# monitoring.net
KiCad netlist of a schematic drawn in EAGLE
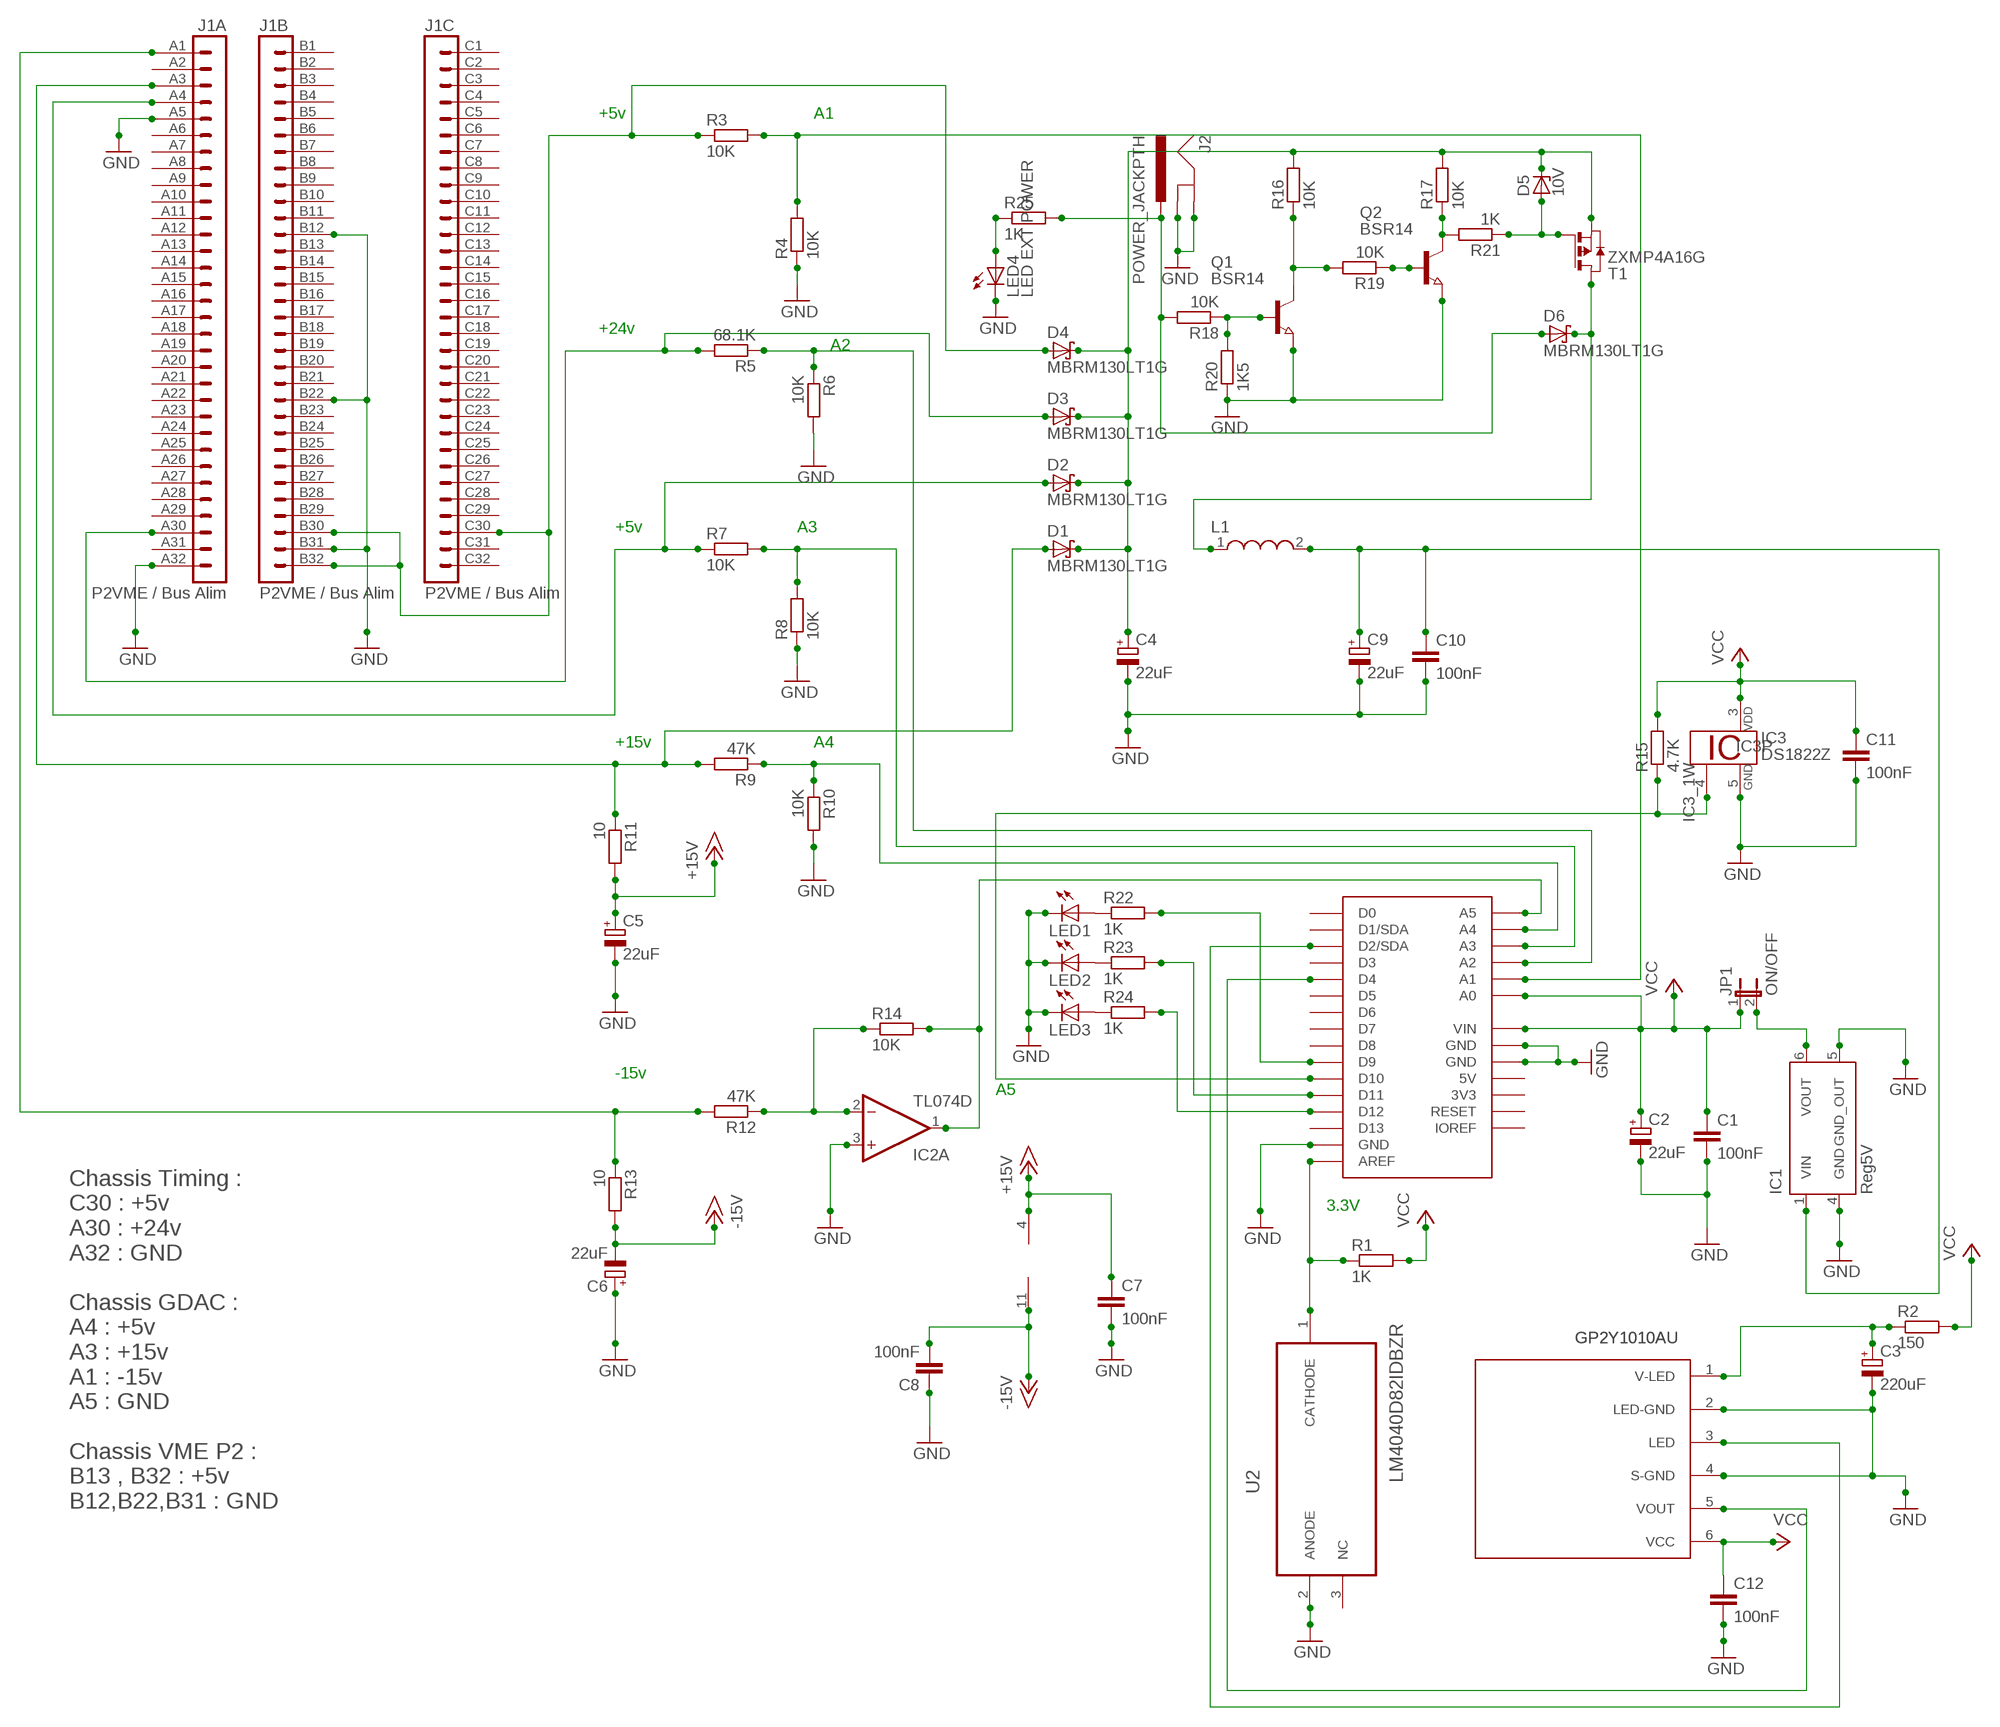
[diagram p0: schematic, sheet 1]

(export (version "E")
  (design (tool "Eeschema 10.0.6"))
  (components
    (comp (ref "C1")
      (value "100nF")
      (footprint "eagle-import:C1206K")
      (libsource (lib "eagle-import") (part "C-EUC1206K"))
    )
    (comp (ref "C2")
      (value "22uF")
      (footprint "eagle-import:CT7343")
      (libsource (lib "eagle-import") (part "CPOL-EUCT7343"))
    )
    (comp (ref "C3")
      (value "220uF")
      (footprint "eagle-import:150CLZ-0810")
      (libsource (lib "eagle-import") (part "CPOL-EU150CLZ-0810"))
    )
    (comp (ref "C4")
      (value "22uF")
      (footprint "eagle-import:CT7343")
      (libsource (lib "eagle-import") (part "CPOL-EUCT7343"))
    )
    (comp (ref "C5")
      (value "22uF")
      (footprint "eagle-import:CT7343")
      (libsource (lib "eagle-import") (part "CPOL-EUCT7343"))
    )
    (comp (ref "C6")
      (value "22uF")
      (footprint "eagle-import:CT7343")
      (libsource (lib "eagle-import") (part "CPOL-EUCT7343"))
    )
    (comp (ref "C7")
      (value "100nF")
      (footprint "eagle-import:C1206K")
      (libsource (lib "eagle-import") (part "C-EUC1206K"))
    )
    (comp (ref "C8")
      (value "100nF")
      (footprint "eagle-import:C1206K")
      (libsource (lib "eagle-import") (part "C-EUC1206K"))
    )
    (comp (ref "C9")
      (value "22uF")
      (footprint "eagle-import:CT7343")
      (libsource (lib "eagle-import") (part "CPOL-EUCT7343"))
    )
    (comp (ref "C10")
      (value "100nF")
      (footprint "eagle-import:C1206K")
      (libsource (lib "eagle-import") (part "C-EUC1206K"))
    )
    (comp (ref "C11")
      (value "100nF")
      (footprint "eagle-import:C1206K")
      (libsource (lib "eagle-import") (part "C-EUC1206K"))
    )
    (comp (ref "C12")
      (value "100nF")
      (footprint "eagle-import:C1206K")
      (libsource (lib "eagle-import") (part "C-EUC1206K"))
    )
    (comp (ref "D1")
      (value "MBRM130LT1G")
      (footprint "eagle-import:DIODE_SMB")
      (libsource (lib "eagle-import") (part "SCHOTTKY-DIODE"))
    )
    (comp (ref "D2")
      (value "MBRM130LT1G")
      (footprint "eagle-import:DIODE_SMB")
      (libsource (lib "eagle-import") (part "SCHOTTKY-DIODE"))
    )
    (comp (ref "D3")
      (value "MBRM130LT1G")
      (footprint "eagle-import:DIODE_SMB")
      (libsource (lib "eagle-import") (part "SCHOTTKY-DIODE"))
    )
    (comp (ref "D4")
      (value "MBRM130LT1G")
      (footprint "eagle-import:DIODE_SMB")
      (libsource (lib "eagle-import") (part "SCHOTTKY-DIODE"))
    )
    (comp (ref "D5")
      (value "10V")
      (footprint "eagle-import:SMB")
      (libsource (lib "eagle-import") (part "ZENER-DIODESMB"))
    )
    (comp (ref "D6")
      (value "MBRM130LT1G")
      (footprint "eagle-import:DIODE_SMB")
      (libsource (lib "eagle-import") (part "SCHOTTKY-DIODE"))
    )
    (comp (ref "IC1")
      (value "Reg5V")
      (footprint "eagle-import:REG5V")
      (libsource (lib "eagle-import") (part "REG5V"))
    )
    (comp (ref "IC2")
      (value "TL074D")
      (footprint "eagle-import:SO14")
      (libsource (lib "eagle-import") (part "TL074D"))
    )
    (comp (ref "IC3")
      (value "DS1822Z")
      (footprint "eagle-import:SO08")
      (libsource (lib "eagle-import") (part "DS1822Z"))
    )
    (comp (ref "J1")
      (value "P2VME / Bus Alim")
      (footprint "eagle-import:VG96")
      (libsource (lib "eagle-import") (part "VG96-3"))
    )
    (comp (ref "J2")
      (value "POWER_JACKPTH")
      (footprint "eagle-import:POWER_JACK_PTH")
      (libsource (lib "eagle-import") (part "POWER_JACKPTH"))
    )
    (comp (ref "JP1")
      (value "ON/OFF")
      (footprint "eagle-import:JP1")
      (libsource (lib "eagle-import") (part "JP1E"))
    )
    (comp (ref "L1")
      (value "WE-UKW_1SW_7427501")
      (footprint "eagle-import:WE-UKW_7427501")
      (libsource (lib "eagle-import") (part "WE-UKW_1SW_7427501"))
    )
    (comp (ref "LED1")
      (value "LED_ELD260")
      (footprint "eagle-import:LED_LD260")
      (libsource (lib "eagle-import") (part "LED_ELD260"))
    )
    (comp (ref "LED2")
      (value "LED_ELD260")
      (footprint "eagle-import:LED_LD260")
      (libsource (lib "eagle-import") (part "LED_ELD260"))
    )
    (comp (ref "LED3")
      (value "LED_ELD260")
      (footprint "eagle-import:LED_LD260")
      (libsource (lib "eagle-import") (part "LED_ELD260"))
    )
    (comp (ref "LED4")
      (value "LED EXT POWER")
      (footprint "eagle-import:LED_LD260")
      (libsource (lib "eagle-import") (part "LED_ELD260"))
    )
    (comp (ref "Q1")
      (value "BSR14")
      (footprint "eagle-import:SOT23")
      (libsource (lib "eagle-import") (part "NPN-TRANSISTOR_SOT23"))
    )
    (comp (ref "Q2")
      (value "BSR14")
      (footprint "eagle-import:SOT23")
      (libsource (lib "eagle-import") (part "NPN-TRANSISTOR_SOT23"))
    )
    (comp (ref "R1")
      (value "1K")
      (footprint "eagle-import:R1206")
      (libsource (lib "eagle-import") (part "R-EU_R1206"))
    )
    (comp (ref "R2")
      (value "150")
      (footprint "eagle-import:R1206")
      (libsource (lib "eagle-import") (part "R-EU_R1206"))
    )
    (comp (ref "R3")
      (value "10K")
      (footprint "eagle-import:R1206")
      (libsource (lib "eagle-import") (part "R-EU_R1206"))
    )
    (comp (ref "R4")
      (value "10K")
      (footprint "eagle-import:R1206")
      (libsource (lib "eagle-import") (part "R-EU_R1206"))
    )
    (comp (ref "R5")
      (value "68.1K")
      (footprint "eagle-import:R1206")
      (libsource (lib "eagle-import") (part "R-EU_R1206"))
    )
    (comp (ref "R6")
      (value "10K")
      (footprint "eagle-import:R1206")
      (libsource (lib "eagle-import") (part "R-EU_R1206"))
    )
    (comp (ref "R7")
      (value "10K")
      (footprint "eagle-import:R1206")
      (libsource (lib "eagle-import") (part "R-EU_R1206"))
    )
    (comp (ref "R8")
      (value "10K")
      (footprint "eagle-import:R1206")
      (libsource (lib "eagle-import") (part "R-EU_R1206"))
    )
    (comp (ref "R9")
      (value "47K")
      (footprint "eagle-import:R1206")
      (libsource (lib "eagle-import") (part "R-EU_R1206"))
    )
    (comp (ref "R10")
      (value "10K")
      (footprint "eagle-import:R1206")
      (libsource (lib "eagle-import") (part "R-EU_R1206"))
    )
    (comp (ref "R11")
      (value "10")
      (footprint "eagle-import:R1206")
      (libsource (lib "eagle-import") (part "R-EU_R1206"))
    )
    (comp (ref "R12")
      (value "47K")
      (footprint "eagle-import:R1206")
      (libsource (lib "eagle-import") (part "R-EU_R1206"))
    )
    (comp (ref "R13")
      (value "10")
      (footprint "eagle-import:R1206")
      (libsource (lib "eagle-import") (part "R-EU_R1206"))
    )
    (comp (ref "R14")
      (value "10K")
      (footprint "eagle-import:R1206")
      (libsource (lib "eagle-import") (part "R-EU_R1206"))
    )
    (comp (ref "R15")
      (value "4.7K")
      (footprint "eagle-import:R1206")
      (libsource (lib "eagle-import") (part "R-EU_R1206"))
    )
    (comp (ref "R16")
      (value "10K")
      (footprint "eagle-import:R1206")
      (libsource (lib "eagle-import") (part "R-EU_R1206"))
    )
    (comp (ref "R17")
      (value "10K")
      (footprint "eagle-import:R1206")
      (libsource (lib "eagle-import") (part "R-EU_R1206"))
    )
    (comp (ref "R18")
      (value "10K")
      (footprint "eagle-import:R1206")
      (libsource (lib "eagle-import") (part "R-EU_R1206"))
    )
    (comp (ref "R19")
      (value "10K")
      (footprint "eagle-import:R1206")
      (libsource (lib "eagle-import") (part "R-EU_R1206"))
    )
    (comp (ref "R20")
      (value "1K5")
      (footprint "eagle-import:R1206")
      (libsource (lib "eagle-import") (part "R-EU_R1206"))
    )
    (comp (ref "R21")
      (value "1K")
      (footprint "eagle-import:R1206")
      (libsource (lib "eagle-import") (part "R-EU_R1206"))
    )
    (comp (ref "R22")
      (value "1K")
      (footprint "eagle-import:R1206")
      (libsource (lib "eagle-import") (part "R-EU_R1206"))
    )
    (comp (ref "R23")
      (value "1K")
      (footprint "eagle-import:R1206")
      (libsource (lib "eagle-import") (part "R-EU_R1206"))
    )
    (comp (ref "R24")
      (value "1K")
      (footprint "eagle-import:R1206")
      (libsource (lib "eagle-import") (part "R-EU_R1206"))
    )
    (comp (ref "R25")
      (value "1K")
      (footprint "eagle-import:R1206")
      (libsource (lib "eagle-import") (part "R-EU_R1206"))
    )
    (comp (ref "T1")
      (value "ZXMP4A16G")
      (footprint "eagle-import:SOT223")
      (libsource (lib "eagle-import") (part "PMOSSOT223"))
    )
    (comp (ref "U$1")
      (value "GP2Y1010AU0F")
      (footprint "eagle-import:GP2Y1010AU")
      (libsource (lib "eagle-import") (part "GP2Y1010AU"))
    )
    (comp (ref "U1")
      (value "YUN_SHIELD-BPLACE")
      (footprint "eagle-import:YUN_SHIELD")
      (libsource (lib "eagle-import") (part "YUN_SHIELD-BPLACE"))
    )
    (comp (ref "U2")
      (value "LM4040D82IDBZR")
      (footprint "eagle-import:SOT95P237X112-3N")
      (libsource (lib "eagle-import") (part "LM4040D82IDBZR"))
    )
  )
  (nets
    (net (code "1") (name "+15V") (class "Default")
      (node (ref "C5") (pin "+") (pinfunction "+_+") (pintype "passive"))
      (node (ref "C7") (pin "1") (pinfunction "1_1") (pintype "passive"))
      (node (ref "IC2") (pin "4") (pinfunction "V+_4") (pintype "power_in"))
      (node (ref "R11") (pin "2") (pinfunction "2_2") (pintype "passive"))
    )
    (net (code "2") (name "-15V") (class "Default")
      (node (ref "C6") (pin "-") (pinfunction "-_-") (pintype "passive"))
      (node (ref "C8") (pin "2") (pinfunction "2_2") (pintype "passive"))
      (node (ref "IC2") (pin "11") (pinfunction "V-_11") (pintype "power_in"))
      (node (ref "R13") (pin "2") (pinfunction "2_2") (pintype "passive"))
    )
    (net (code "3") (name "/3V3") (class "Default")
      (node (ref "U1") (pin "3V3") (pinfunction "3V3_3V3") (pintype "power_in"))
    )
    (net (code "4") (name "/5V") (class "Default")
      (node (ref "U1") (pin "5V") (pinfunction "5V_5V") (pintype "power_in"))
    )
    (net (code "5") (name "/IOREF") (class "Default")
      (node (ref "U1") (pin "IOREF") (pinfunction "IOREF_IOREF") (pintype "power_in"))
    )
    (net (code "6") (name "GND") (class "Default")
      (node (ref "C1") (pin "2") (pinfunction "2_2") (pintype "passive"))
      (node (ref "C10") (pin "2") (pinfunction "2_2") (pintype "passive"))
      (node (ref "C11") (pin "2") (pinfunction "2_2") (pintype "passive"))
      (node (ref "C12") (pin "2") (pinfunction "2_2") (pintype "passive"))
      (node (ref "C2") (pin "-") (pinfunction "-_-") (pintype "passive"))
      (node (ref "C3") (pin "-") (pinfunction "-_-") (pintype "passive"))
      (node (ref "C4") (pin "-") (pinfunction "-_-") (pintype "passive"))
      (node (ref "C5") (pin "-") (pinfunction "-_-") (pintype "passive"))
      (node (ref "C6") (pin "+") (pinfunction "+_+") (pintype "passive"))
      (node (ref "C7") (pin "2") (pinfunction "2_2") (pintype "passive"))
      (node (ref "C8") (pin "1") (pinfunction "1_1") (pintype "passive"))
      (node (ref "C9") (pin "-") (pinfunction "-_-") (pintype "passive"))
      (node (ref "IC1") (pin "4") (pinfunction "GND_4") (pintype "power_in"))
      (node (ref "IC1") (pin "5") (pinfunction "GND_OUT_5") (pintype "power_in"))
      (node (ref "IC2") (pin "3") (pinfunction "+IN_3") (pintype "input"))
      (node (ref "IC3") (pin "5") (pinfunction "GND_5") (pintype "power_in"))
      (node (ref "J1") (pin "A32") (pinfunction "32_A32") (pintype "passive"))
      (node (ref "J1") (pin "A5") (pinfunction "5_A5") (pintype "passive"))
      (node (ref "J1") (pin "B12") (pinfunction "12_B12") (pintype "passive"))
      (node (ref "J1") (pin "B22") (pinfunction "22_B22") (pintype "passive"))
      (node (ref "J1") (pin "B31") (pinfunction "31_B31") (pintype "passive"))
      (node (ref "J2") (pin "GND") (pinfunction "GND_GND") (pintype "bidirectional"))
      (node (ref "J2") (pin "GNDBREAK") (pinfunction "GNDBREAK_GNDBREAK") (pintype "bidirectional"))
      (node (ref "LED1") (pin "K") (pinfunction "C_K") (pintype "passive"))
      (node (ref "LED2") (pin "K") (pinfunction "C_K") (pintype "passive"))
      (node (ref "LED3") (pin "K") (pinfunction "C_K") (pintype "passive"))
      (node (ref "LED4") (pin "K") (pinfunction "C_K") (pintype "passive"))
      (node (ref "Q1") (pin "2") (pinfunction "E_2") (pintype "passive"))
      (node (ref "Q2") (pin "2") (pinfunction "E_2") (pintype "passive"))
      (node (ref "R10") (pin "2") (pinfunction "2_2") (pintype "passive"))
      (node (ref "R20") (pin "1") (pinfunction "1_1") (pintype "passive"))
      (node (ref "R4") (pin "1") (pinfunction "1_1") (pintype "passive"))
      (node (ref "R6") (pin "2") (pinfunction "2_2") (pintype "passive"))
      (node (ref "R8") (pin "1") (pinfunction "1_1") (pintype "passive"))
      (node (ref "U$1") (pin "2") (pinfunction "LED-GND_2") (pintype "power_in"))
      (node (ref "U$1") (pin "4") (pinfunction "S-GND_4") (pintype "power_in"))
      (node (ref "U1") (pin "GND@1") (pinfunction "GND_GND@1") (pintype "power_in"))
      (node (ref "U1") (pin "GND@2") (pinfunction "GND_GND@2") (pintype "power_in"))
      (node (ref "U1") (pin "GND@3") (pinfunction "GND_GND@3") (pintype "power_in"))
      (node (ref "U2") (pin "2") (pinfunction "ANODE_2") (pintype "input"))
    )
    (net (code "7") (name "Net-(D1-A)") (class "Default")
      (node (ref "C4") (pin "+") (pinfunction "+_+") (pintype "passive"))
      (node (ref "D1") (pin "C") (pinfunction "A_C") (pintype "passive"))
      (node (ref "D2") (pin "C") (pinfunction "A_C") (pintype "passive"))
      (node (ref "D3") (pin "C") (pinfunction "A_C") (pintype "passive"))
      (node (ref "D4") (pin "C") (pinfunction "A_C") (pintype "passive"))
      (node (ref "D5") (pin "C") (pinfunction "C_C") (pintype "passive"))
      (node (ref "R16") (pin "2") (pinfunction "2_2") (pintype "passive"))
      (node (ref "R17") (pin "2") (pinfunction "2_2") (pintype "passive"))
      (node (ref "T1") (pin "3") (pinfunction "S_3") (pintype "passive"))
    )
    (net (code "8") (name "Net-(D1-C)") (class "Default")
      (node (ref "D1") (pin "A") (pinfunction "C_A") (pintype "passive"))
      (node (ref "J1") (pin "A3") (pinfunction "3_A3") (pintype "passive"))
      (node (ref "R11") (pin "1") (pinfunction "1_1") (pintype "passive"))
      (node (ref "R9") (pin "2") (pinfunction "2_2") (pintype "passive"))
    )
    (net (code "9") (name "Net-(D2-C)") (class "Default")
      (node (ref "D2") (pin "A") (pinfunction "C_A") (pintype "passive"))
      (node (ref "J1") (pin "A4") (pinfunction "4_A4") (pintype "passive"))
      (node (ref "R7") (pin "1") (pinfunction "1_1") (pintype "passive"))
    )
    (net (code "10") (name "Net-(D3-C)") (class "Default")
      (node (ref "D3") (pin "A") (pinfunction "C_A") (pintype "passive"))
      (node (ref "J1") (pin "A30") (pinfunction "30_A30") (pintype "passive"))
      (node (ref "R5") (pin "2") (pinfunction "2_2") (pintype "passive"))
    )
    (net (code "11") (name "Net-(D4-C)") (class "Default")
      (node (ref "D4") (pin "A") (pinfunction "C_A") (pintype "passive"))
      (node (ref "J1") (pin "B30") (pinfunction "30_B30") (pintype "passive"))
      (node (ref "J1") (pin "B32") (pinfunction "32_B32") (pintype "passive"))
      (node (ref "J1") (pin "C30") (pinfunction "30_C30") (pintype "passive"))
      (node (ref "R3") (pin "1") (pinfunction "1_1") (pintype "passive"))
    )
    (net (code "12") (name "Net-(D6-A)") (class "Default")
      (node (ref "D6") (pin "C") (pinfunction "A_C") (pintype "passive"))
      (node (ref "L1") (pin "1") (pinfunction "1_1") (pintype "passive"))
      (node (ref "T1") (pin "2") (pinfunction "D_2") (pintype "passive"))
      (node (ref "T1") (pin "4") (pinfunction "D_4") (pintype "passive"))
    )
    (net (code "13") (name "Net-(D6-C)") (class "Default")
      (node (ref "D6") (pin "A") (pinfunction "C_A") (pintype "passive"))
      (node (ref "J2") (pin "PWR") (pinfunction "PWR_PWR") (pintype "bidirectional"))
      (node (ref "R18") (pin "2") (pinfunction "2_2") (pintype "passive"))
      (node (ref "R25") (pin "2") (pinfunction "2_2") (pintype "passive"))
    )
    (net (code "14") (name "Net-(IC1-VIN)") (class "Default")
      (node (ref "C10") (pin "1") (pinfunction "1_1") (pintype "passive"))
      (node (ref "C9") (pin "+") (pinfunction "+_+") (pintype "passive"))
      (node (ref "IC1") (pin "1") (pinfunction "VIN_1") (pintype "input"))
      (node (ref "L1") (pin "2") (pinfunction "2_2") (pintype "passive"))
    )
    (net (code "15") (name "Net-(IC1-VOUT)") (class "Default")
      (node (ref "IC1") (pin "6") (pinfunction "VOUT_6") (pintype "output"))
      (node (ref "JP1") (pin "2") (pinfunction "2_2") (pintype "passive"))
    )
    (net (code "16") (name "Net-(IC2A--IN)") (class "Default")
      (node (ref "IC2") (pin "2") (pinfunction "-IN_2") (pintype "input"))
      (node (ref "R12") (pin "1") (pinfunction "1_1") (pintype "passive"))
      (node (ref "R14") (pin "1") (pinfunction "1_1") (pintype "passive"))
    )
    (net (code "17") (name "Net-(IC2A-OUT)") (class "Default")
      (node (ref "IC2") (pin "1") (pinfunction "OUT_1") (pintype "output"))
      (node (ref "R14") (pin "2") (pinfunction "2_2") (pintype "passive"))
      (node (ref "U1") (pin "A5") (pinfunction "A5_A5") (pintype "bidirectional"))
    )
    (net (code "18") (name "Net-(IC3C-1W)") (class "Default")
      (node (ref "IC3") (pin "4") (pinfunction "1W_4") (pintype "power_in"))
      (node (ref "R15") (pin "1") (pinfunction "1_1") (pintype "passive"))
      (node (ref "U1") (pin "D10") (pinfunction "D10_D10") (pintype "bidirectional"))
    )
    (net (code "19") (name "Net-(J1A-1)") (class "Default")
      (node (ref "J1") (pin "A1") (pinfunction "1_A1") (pintype "passive"))
      (node (ref "R12") (pin "2") (pinfunction "2_2") (pintype "passive"))
      (node (ref "R13") (pin "1") (pinfunction "1_1") (pintype "passive"))
    )
    (net (code "20") (name "Net-(LED1-PadA)") (class "Default")
      (node (ref "LED1") (pin "A") (pinfunction "A_A") (pintype "passive"))
      (node (ref "R22") (pin "1") (pinfunction "1_1") (pintype "passive"))
    )
    (net (code "21") (name "Net-(LED2-PadA)") (class "Default")
      (node (ref "LED2") (pin "A") (pinfunction "A_A") (pintype "passive"))
      (node (ref "R23") (pin "1") (pinfunction "1_1") (pintype "passive"))
    )
    (net (code "22") (name "Net-(LED3-PadA)") (class "Default")
      (node (ref "LED3") (pin "A") (pinfunction "A_A") (pintype "passive"))
      (node (ref "R24") (pin "1") (pinfunction "1_1") (pintype "passive"))
    )
    (net (code "23") (name "Net-(LED4-PadA)") (class "Default")
      (node (ref "LED4") (pin "A") (pinfunction "A_A") (pintype "passive"))
      (node (ref "R25") (pin "1") (pinfunction "1_1") (pintype "passive"))
    )
    (net (code "24") (name "Net-(Q1-B)") (class "Default")
      (node (ref "Q1") (pin "1") (pinfunction "B_1") (pintype "passive"))
      (node (ref "R18") (pin "1") (pinfunction "1_1") (pintype "passive"))
      (node (ref "R20") (pin "2") (pinfunction "2_2") (pintype "passive"))
    )
    (net (code "25") (name "Net-(Q1-C)") (class "Default")
      (node (ref "Q1") (pin "3") (pinfunction "C_3") (pintype "passive"))
      (node (ref "R16") (pin "1") (pinfunction "1_1") (pintype "passive"))
      (node (ref "R19") (pin "2") (pinfunction "2_2") (pintype "passive"))
    )
    (net (code "26") (name "Net-(Q2-B)") (class "Default")
      (node (ref "Q2") (pin "1") (pinfunction "B_1") (pintype "passive"))
      (node (ref "R19") (pin "1") (pinfunction "1_1") (pintype "passive"))
    )
    (net (code "27") (name "Net-(Q2-C)") (class "Default")
      (node (ref "Q2") (pin "3") (pinfunction "C_3") (pintype "passive"))
      (node (ref "R17") (pin "1") (pinfunction "1_1") (pintype "passive"))
      (node (ref "R21") (pin "2") (pinfunction "2_2") (pintype "passive"))
    )
    (net (code "28") (name "Net-(R3-Pad2)") (class "Default")
      (node (ref "R3") (pin "2") (pinfunction "2_2") (pintype "passive"))
      (node (ref "R4") (pin "2") (pinfunction "2_2") (pintype "passive"))
      (node (ref "U1") (pin "A1") (pinfunction "A1_A1") (pintype "bidirectional"))
    )
    (net (code "29") (name "Net-(R5-Pad1)") (class "Default")
      (node (ref "R5") (pin "1") (pinfunction "1_1") (pintype "passive"))
      (node (ref "R6") (pin "1") (pinfunction "1_1") (pintype "passive"))
      (node (ref "U1") (pin "A2") (pinfunction "A2_A2") (pintype "bidirectional"))
    )
    (net (code "30") (name "Net-(R7-Pad2)") (class "Default")
      (node (ref "R7") (pin "2") (pinfunction "2_2") (pintype "passive"))
      (node (ref "R8") (pin "2") (pinfunction "2_2") (pintype "passive"))
      (node (ref "U1") (pin "A3") (pinfunction "A3_A3") (pintype "bidirectional"))
    )
    (net (code "31") (name "Net-(R10-Pad1)") (class "Default")
      (node (ref "R10") (pin "1") (pinfunction "1_1") (pintype "passive"))
      (node (ref "R9") (pin "1") (pinfunction "1_1") (pintype "passive"))
      (node (ref "U1") (pin "A4") (pinfunction "A4_A4") (pintype "bidirectional"))
    )
    (net (code "32") (name "Net-(R22-Pad2)") (class "Default")
      (node (ref "R22") (pin "2") (pinfunction "2_2") (pintype "passive"))
      (node (ref "U1") (pin "D9") (pinfunction "D9_D9") (pintype "bidirectional"))
    )
    (net (code "33") (name "Net-(R23-Pad2)") (class "Default")
      (node (ref "R23") (pin "2") (pinfunction "2_2") (pintype "passive"))
      (node (ref "U1") (pin "D11") (pinfunction "D11_D11") (pintype "bidirectional"))
    )
    (net (code "34") (name "Net-(R24-Pad2)") (class "Default")
      (node (ref "R24") (pin "2") (pinfunction "2_2") (pintype "passive"))
      (node (ref "U1") (pin "D12") (pinfunction "D12_D12") (pintype "bidirectional"))
    )
    (net (code "35") (name "Net-(T1-G)") (class "Default")
      (node (ref "D5") (pin "A") (pinfunction "A_A") (pintype "passive"))
      (node (ref "R21") (pin "1") (pinfunction "1_1") (pintype "passive"))
      (node (ref "T1") (pin "1") (pinfunction "G_1") (pintype "passive"))
    )
    (net (code "36") (name "Net-(U$1-LED)") (class "Default")
      (node (ref "U$1") (pin "3") (pinfunction "LED_3") (pintype "input"))
      (node (ref "U1") (pin "D2") (pinfunction "D2/SDA_D2") (pintype "bidirectional"))
    )
    (net (code "37") (name "Net-(U$1-V-LED)") (class "Default")
      (node (ref "C3") (pin "+") (pinfunction "+_+") (pintype "passive"))
      (node (ref "R2") (pin "1") (pinfunction "1_1") (pintype "passive"))
      (node (ref "U$1") (pin "1") (pinfunction "V-LED_1") (pintype "power_in"))
    )
    (net (code "38") (name "Net-(U$1-VOUT)") (class "Default")
      (node (ref "U$1") (pin "5") (pinfunction "VOUT_5") (pintype "output"))
      (node (ref "U1") (pin "D4") (pinfunction "D4_D4") (pintype "bidirectional"))
    )
    (net (code "39") (name "Net-(U2-CATHODE)") (class "Default")
      (node (ref "R1") (pin "1") (pinfunction "1_1") (pintype "passive"))
      (node (ref "U1") (pin "AREF") (pinfunction "AREF_AREF") (pintype "power_in"))
      (node (ref "U2") (pin "1") (pinfunction "CATHODE_1") (pintype "output"))
    )
    (net (code "40") (name "VCC") (class "Default")
      (node (ref "C1") (pin "1") (pinfunction "1_1") (pintype "passive"))
      (node (ref "C11") (pin "1") (pinfunction "1_1") (pintype "passive"))
      (node (ref "C12") (pin "1") (pinfunction "1_1") (pintype "passive"))
      (node (ref "C2") (pin "+") (pinfunction "+_+") (pintype "passive"))
      (node (ref "IC3") (pin "3") (pinfunction "VDD_3") (pintype "power_in"))
      (node (ref "JP1") (pin "1") (pinfunction "1_1") (pintype "passive"))
      (node (ref "R1") (pin "2") (pinfunction "2_2") (pintype "passive"))
      (node (ref "R15") (pin "2") (pinfunction "2_2") (pintype "passive"))
      (node (ref "R2") (pin "2") (pinfunction "2_2") (pintype "passive"))
      (node (ref "U$1") (pin "6") (pinfunction "VCC_6") (pintype "power_in"))
      (node (ref "U1") (pin "A0") (pinfunction "A0_A0") (pintype "bidirectional"))
      (node (ref "U1") (pin "VIN") (pinfunction "VIN_VIN") (pintype "power_in"))
    )
    (net (code "41") (name "unconnected-(J1A-2-PadA2)") (class "Default")
      (node (ref "J1") (pin "A2") (pinfunction "2_A2") (pintype "passive"))
    )
    (net (code "42") (name "unconnected-(J1A-6-PadA6)") (class "Default")
      (node (ref "J1") (pin "A6") (pinfunction "6_A6") (pintype "passive"))
    )
    (net (code "43") (name "unconnected-(J1A-7-PadA7)") (class "Default")
      (node (ref "J1") (pin "A7") (pinfunction "7_A7") (pintype "passive"))
    )
    (net (code "44") (name "unconnected-(J1A-8-PadA8)") (class "Default")
      (node (ref "J1") (pin "A8") (pinfunction "8_A8") (pintype "passive"))
    )
    (net (code "45") (name "unconnected-(J1A-9-PadA9)") (class "Default")
      (node (ref "J1") (pin "A9") (pinfunction "9_A9") (pintype "passive"))
    )
    (net (code "46") (name "unconnected-(J1A-10-PadA10)") (class "Default")
      (node (ref "J1") (pin "A10") (pinfunction "10_A10") (pintype "passive"))
    )
    (net (code "47") (name "unconnected-(J1A-11-PadA11)") (class "Default")
      (node (ref "J1") (pin "A11") (pinfunction "11_A11") (pintype "passive"))
    )
    (net (code "48") (name "unconnected-(J1A-12-PadA12)") (class "Default")
      (node (ref "J1") (pin "A12") (pinfunction "12_A12") (pintype "passive"))
    )
    (net (code "49") (name "unconnected-(J1A-13-PadA13)") (class "Default")
      (node (ref "J1") (pin "A13") (pinfunction "13_A13") (pintype "passive"))
    )
    (net (code "50") (name "unconnected-(J1A-14-PadA14)") (class "Default")
      (node (ref "J1") (pin "A14") (pinfunction "14_A14") (pintype "passive"))
    )
    (net (code "51") (name "unconnected-(J1A-15-PadA15)") (class "Default")
      (node (ref "J1") (pin "A15") (pinfunction "15_A15") (pintype "passive"))
    )
    (net (code "52") (name "unconnected-(J1A-16-PadA16)") (class "Default")
      (node (ref "J1") (pin "A16") (pinfunction "16_A16") (pintype "passive"))
    )
    (net (code "53") (name "unconnected-(J1A-17-PadA17)") (class "Default")
      (node (ref "J1") (pin "A17") (pinfunction "17_A17") (pintype "passive"))
    )
    (net (code "54") (name "unconnected-(J1A-18-PadA18)") (class "Default")
      (node (ref "J1") (pin "A18") (pinfunction "18_A18") (pintype "passive"))
    )
    (net (code "55") (name "unconnected-(J1A-19-PadA19)") (class "Default")
      (node (ref "J1") (pin "A19") (pinfunction "19_A19") (pintype "passive"))
    )
    (net (code "56") (name "unconnected-(J1A-20-PadA20)") (class "Default")
      (node (ref "J1") (pin "A20") (pinfunction "20_A20") (pintype "passive"))
    )
    (net (code "57") (name "unconnected-(J1A-21-PadA21)") (class "Default")
      (node (ref "J1") (pin "A21") (pinfunction "21_A21") (pintype "passive"))
    )
    (net (code "58") (name "unconnected-(J1A-22-PadA22)") (class "Default")
      (node (ref "J1") (pin "A22") (pinfunction "22_A22") (pintype "passive"))
    )
    (net (code "59") (name "unconnected-(J1A-23-PadA23)") (class "Default")
      (node (ref "J1") (pin "A23") (pinfunction "23_A23") (pintype "passive"))
    )
    (net (code "60") (name "unconnected-(J1A-24-PadA24)") (class "Default")
      (node (ref "J1") (pin "A24") (pinfunction "24_A24") (pintype "passive"))
    )
    (net (code "61") (name "unconnected-(J1A-25-PadA25)") (class "Default")
      (node (ref "J1") (pin "A25") (pinfunction "25_A25") (pintype "passive"))
    )
    (net (code "62") (name "unconnected-(J1A-26-PadA26)") (class "Default")
      (node (ref "J1") (pin "A26") (pinfunction "26_A26") (pintype "passive"))
    )
    (net (code "63") (name "unconnected-(J1A-27-PadA27)") (class "Default")
      (node (ref "J1") (pin "A27") (pinfunction "27_A27") (pintype "passive"))
    )
    (net (code "64") (name "unconnected-(J1A-28-PadA28)") (class "Default")
      (node (ref "J1") (pin "A28") (pinfunction "28_A28") (pintype "passive"))
    )
    (net (code "65") (name "unconnected-(J1A-29-PadA29)") (class "Default")
      (node (ref "J1") (pin "A29") (pinfunction "29_A29") (pintype "passive"))
    )
    (net (code "66") (name "unconnected-(J1A-31-PadA31)") (class "Default")
      (node (ref "J1") (pin "A31") (pinfunction "31_A31") (pintype "passive"))
    )
    (net (code "67") (name "unconnected-(J1B-1-PadB1)") (class "Default")
      (node (ref "J1") (pin "B1") (pinfunction "1_B1") (pintype "passive"))
    )
    (net (code "68") (name "unconnected-(J1B-2-PadB2)") (class "Default")
      (node (ref "J1") (pin "B2") (pinfunction "2_B2") (pintype "passive"))
    )
    (net (code "69") (name "unconnected-(J1B-3-PadB3)") (class "Default")
      (node (ref "J1") (pin "B3") (pinfunction "3_B3") (pintype "passive"))
    )
    (net (code "70") (name "unconnected-(J1B-4-PadB4)") (class "Default")
      (node (ref "J1") (pin "B4") (pinfunction "4_B4") (pintype "passive"))
    )
    (net (code "71") (name "unconnected-(J1B-5-PadB5)") (class "Default")
      (node (ref "J1") (pin "B5") (pinfunction "5_B5") (pintype "passive"))
    )
    (net (code "72") (name "unconnected-(J1B-6-PadB6)") (class "Default")
      (node (ref "J1") (pin "B6") (pinfunction "6_B6") (pintype "passive"))
    )
    (net (code "73") (name "unconnected-(J1B-7-PadB7)") (class "Default")
      (node (ref "J1") (pin "B7") (pinfunction "7_B7") (pintype "passive"))
    )
    (net (code "74") (name "unconnected-(J1B-8-PadB8)") (class "Default")
      (node (ref "J1") (pin "B8") (pinfunction "8_B8") (pintype "passive"))
    )
    (net (code "75") (name "unconnected-(J1B-9-PadB9)") (class "Default")
      (node (ref "J1") (pin "B9") (pinfunction "9_B9") (pintype "passive"))
    )
    (net (code "76") (name "unconnected-(J1B-10-PadB10)") (class "Default")
      (node (ref "J1") (pin "B10") (pinfunction "10_B10") (pintype "passive"))
    )
    (net (code "77") (name "unconnected-(J1B-11-PadB11)") (class "Default")
      (node (ref "J1") (pin "B11") (pinfunction "11_B11") (pintype "passive"))
    )
    (net (code "78") (name "unconnected-(J1B-13-PadB13)") (class "Default")
      (node (ref "J1") (pin "B13") (pinfunction "13_B13") (pintype "passive"))
    )
    (net (code "79") (name "unconnected-(J1B-14-PadB14)") (class "Default")
      (node (ref "J1") (pin "B14") (pinfunction "14_B14") (pintype "passive"))
    )
    (net (code "80") (name "unconnected-(J1B-15-PadB15)") (class "Default")
      (node (ref "J1") (pin "B15") (pinfunction "15_B15") (pintype "passive"))
    )
    (net (code "81") (name "unconnected-(J1B-16-PadB16)") (class "Default")
      (node (ref "J1") (pin "B16") (pinfunction "16_B16") (pintype "passive"))
    )
    (net (code "82") (name "unconnected-(J1B-17-PadB17)") (class "Default")
      (node (ref "J1") (pin "B17") (pinfunction "17_B17") (pintype "passive"))
    )
    (net (code "83") (name "unconnected-(J1B-18-PadB18)") (class "Default")
      (node (ref "J1") (pin "B18") (pinfunction "18_B18") (pintype "passive"))
    )
    (net (code "84") (name "unconnected-(J1B-19-PadB19)") (class "Default")
      (node (ref "J1") (pin "B19") (pinfunction "19_B19") (pintype "passive"))
    )
    (net (code "85") (name "unconnected-(J1B-20-PadB20)") (class "Default")
      (node (ref "J1") (pin "B20") (pinfunction "20_B20") (pintype "passive"))
    )
    (net (code "86") (name "unconnected-(J1B-21-PadB21)") (class "Default")
      (node (ref "J1") (pin "B21") (pinfunction "21_B21") (pintype "passive"))
    )
    (net (code "87") (name "unconnected-(J1B-23-PadB23)") (class "Default")
      (node (ref "J1") (pin "B23") (pinfunction "23_B23") (pintype "passive"))
    )
    (net (code "88") (name "unconnected-(J1B-24-PadB24)") (class "Default")
      (node (ref "J1") (pin "B24") (pinfunction "24_B24") (pintype "passive"))
    )
    (net (code "89") (name "unconnected-(J1B-25-PadB25)") (class "Default")
      (node (ref "J1") (pin "B25") (pinfunction "25_B25") (pintype "passive"))
    )
    (net (code "90") (name "unconnected-(J1B-26-PadB26)") (class "Default")
      (node (ref "J1") (pin "B26") (pinfunction "26_B26") (pintype "passive"))
    )
    (net (code "91") (name "unconnected-(J1B-27-PadB27)") (class "Default")
      (node (ref "J1") (pin "B27") (pinfunction "27_B27") (pintype "passive"))
    )
    (net (code "92") (name "unconnected-(J1B-28-PadB28)") (class "Default")
      (node (ref "J1") (pin "B28") (pinfunction "28_B28") (pintype "passive"))
    )
    (net (code "93") (name "unconnected-(J1B-29-PadB29)") (class "Default")
      (node (ref "J1") (pin "B29") (pinfunction "29_B29") (pintype "passive"))
    )
    (net (code "94") (name "unconnected-(J1C-1-PadC1)") (class "Default")
      (node (ref "J1") (pin "C1") (pinfunction "1_C1") (pintype "passive"))
    )
    (net (code "95") (name "unconnected-(J1C-2-PadC2)") (class "Default")
      (node (ref "J1") (pin "C2") (pinfunction "2_C2") (pintype "passive"))
    )
    (net (code "96") (name "unconnected-(J1C-3-PadC3)") (class "Default")
      (node (ref "J1") (pin "C3") (pinfunction "3_C3") (pintype "passive"))
    )
    (net (code "97") (name "unconnected-(J1C-4-PadC4)") (class "Default")
      (node (ref "J1") (pin "C4") (pinfunction "4_C4") (pintype "passive"))
    )
    (net (code "98") (name "unconnected-(J1C-5-PadC5)") (class "Default")
      (node (ref "J1") (pin "C5") (pinfunction "5_C5") (pintype "passive"))
    )
    (net (code "99") (name "unconnected-(J1C-6-PadC6)") (class "Default")
      (node (ref "J1") (pin "C6") (pinfunction "6_C6") (pintype "passive"))
    )
    (net (code "100") (name "unconnected-(J1C-7-PadC7)") (class "Default")
      (node (ref "J1") (pin "C7") (pinfunction "7_C7") (pintype "passive"))
    )
    (net (code "101") (name "unconnected-(J1C-8-PadC8)") (class "Default")
      (node (ref "J1") (pin "C8") (pinfunction "8_C8") (pintype "passive"))
    )
    (net (code "102") (name "unconnected-(J1C-9-PadC9)") (class "Default")
      (node (ref "J1") (pin "C9") (pinfunction "9_C9") (pintype "passive"))
    )
    (net (code "103") (name "unconnected-(J1C-10-PadC10)") (class "Default")
      (node (ref "J1") (pin "C10") (pinfunction "10_C10") (pintype "passive"))
    )
    (net (code "104") (name "unconnected-(J1C-11-PadC11)") (class "Default")
      (node (ref "J1") (pin "C11") (pinfunction "11_C11") (pintype "passive"))
    )
    (net (code "105") (name "unconnected-(J1C-12-PadC12)") (class "Default")
      (node (ref "J1") (pin "C12") (pinfunction "12_C12") (pintype "passive"))
    )
    (net (code "106") (name "unconnected-(J1C-13-PadC13)") (class "Default")
      (node (ref "J1") (pin "C13") (pinfunction "13_C13") (pintype "passive"))
    )
    (net (code "107") (name "unconnected-(J1C-14-PadC14)") (class "Default")
      (node (ref "J1") (pin "C14") (pinfunction "14_C14") (pintype "passive"))
    )
    (net (code "108") (name "unconnected-(J1C-15-PadC15)") (class "Default")
      (node (ref "J1") (pin "C15") (pinfunction "15_C15") (pintype "passive"))
    )
    (net (code "109") (name "unconnected-(J1C-16-PadC16)") (class "Default")
      (node (ref "J1") (pin "C16") (pinfunction "16_C16") (pintype "passive"))
    )
    (net (code "110") (name "unconnected-(J1C-17-PadC17)") (class "Default")
      (node (ref "J1") (pin "C17") (pinfunction "17_C17") (pintype "passive"))
    )
    (net (code "111") (name "unconnected-(J1C-18-PadC18)") (class "Default")
      (node (ref "J1") (pin "C18") (pinfunction "18_C18") (pintype "passive"))
    )
    (net (code "112") (name "unconnected-(J1C-19-PadC19)") (class "Default")
      (node (ref "J1") (pin "C19") (pinfunction "19_C19") (pintype "passive"))
    )
    (net (code "113") (name "unconnected-(J1C-20-PadC20)") (class "Default")
      (node (ref "J1") (pin "C20") (pinfunction "20_C20") (pintype "passive"))
    )
    (net (code "114") (name "unconnected-(J1C-21-PadC21)") (class "Default")
      (node (ref "J1") (pin "C21") (pinfunction "21_C21") (pintype "passive"))
    )
    (net (code "115") (name "unconnected-(J1C-22-PadC22)") (class "Default")
      (node (ref "J1") (pin "C22") (pinfunction "22_C22") (pintype "passive"))
    )
    (net (code "116") (name "unconnected-(J1C-23-PadC23)") (class "Default")
      (node (ref "J1") (pin "C23") (pinfunction "23_C23") (pintype "passive"))
    )
    (net (code "117") (name "unconnected-(J1C-24-PadC24)") (class "Default")
      (node (ref "J1") (pin "C24") (pinfunction "24_C24") (pintype "passive"))
    )
    (net (code "118") (name "unconnected-(J1C-25-PadC25)") (class "Default")
      (node (ref "J1") (pin "C25") (pinfunction "25_C25") (pintype "passive"))
    )
    (net (code "119") (name "unconnected-(J1C-26-PadC26)") (class "Default")
      (node (ref "J1") (pin "C26") (pinfunction "26_C26") (pintype "passive"))
    )
    (net (code "120") (name "unconnected-(J1C-27-PadC27)") (class "Default")
      (node (ref "J1") (pin "C27") (pinfunction "27_C27") (pintype "passive"))
    )
    (net (code "121") (name "unconnected-(J1C-28-PadC28)") (class "Default")
      (node (ref "J1") (pin "C28") (pinfunction "28_C28") (pintype "passive"))
    )
    (net (code "122") (name "unconnected-(J1C-29-PadC29)") (class "Default")
      (node (ref "J1") (pin "C29") (pinfunction "29_C29") (pintype "passive"))
    )
    (net (code "123") (name "unconnected-(J1C-31-PadC31)") (class "Default")
      (node (ref "J1") (pin "C31") (pinfunction "31_C31") (pintype "passive"))
    )
    (net (code "124") (name "unconnected-(J1C-32-PadC32)") (class "Default")
      (node (ref "J1") (pin "C32") (pinfunction "32_C32") (pintype "passive"))
    )
    (net (code "125") (name "unconnected-(U1-D1{slash}SDA-PadD1)") (class "Default")
      (node (ref "U1") (pin "D1") (pinfunction "D1/SDA_D1") (pintype "bidirectional"))
    )
    (net (code "126") (name "unconnected-(U1-PadD0)") (class "Default")
      (node (ref "U1") (pin "D0") (pinfunction "D0_D0") (pintype "bidirectional"))
    )
    (net (code "127") (name "unconnected-(U1-PadD3)") (class "Default")
      (node (ref "U1") (pin "D3") (pinfunction "D3_D3") (pintype "bidirectional"))
    )
    (net (code "128") (name "unconnected-(U1-PadD5)") (class "Default")
      (node (ref "U1") (pin "D5") (pinfunction "D5_D5") (pintype "bidirectional"))
    )
    (net (code "129") (name "unconnected-(U1-PadD6)") (class "Default")
      (node (ref "U1") (pin "D6") (pinfunction "D6_D6") (pintype "bidirectional"))
    )
    (net (code "130") (name "unconnected-(U1-PadD7)") (class "Default")
      (node (ref "U1") (pin "D7") (pinfunction "D7_D7") (pintype "bidirectional"))
    )
    (net (code "131") (name "unconnected-(U1-PadD8)") (class "Default")
      (node (ref "U1") (pin "D8") (pinfunction "D8_D8") (pintype "bidirectional"))
    )
    (net (code "132") (name "unconnected-(U1-PadD13)") (class "Default")
      (node (ref "U1") (pin "D13") (pinfunction "D13_D13") (pintype "bidirectional"))
    )
    (net (code "133") (name "unconnected-(U1-PadRESET)") (class "Default")
      (node (ref "U1") (pin "RESET") (pinfunction "RESET_RESET") (pintype "bidirectional"))
    )
    (net (code "134") (name "unconnected-(U2-NC-Pad3)") (class "Default")
      (node (ref "U2") (pin "3") (pinfunction "NC_3") (pintype "no_connect"))
    )
  )
)
